# MCU.net
KiCad netlist of a schematic drawn in Altium Designer
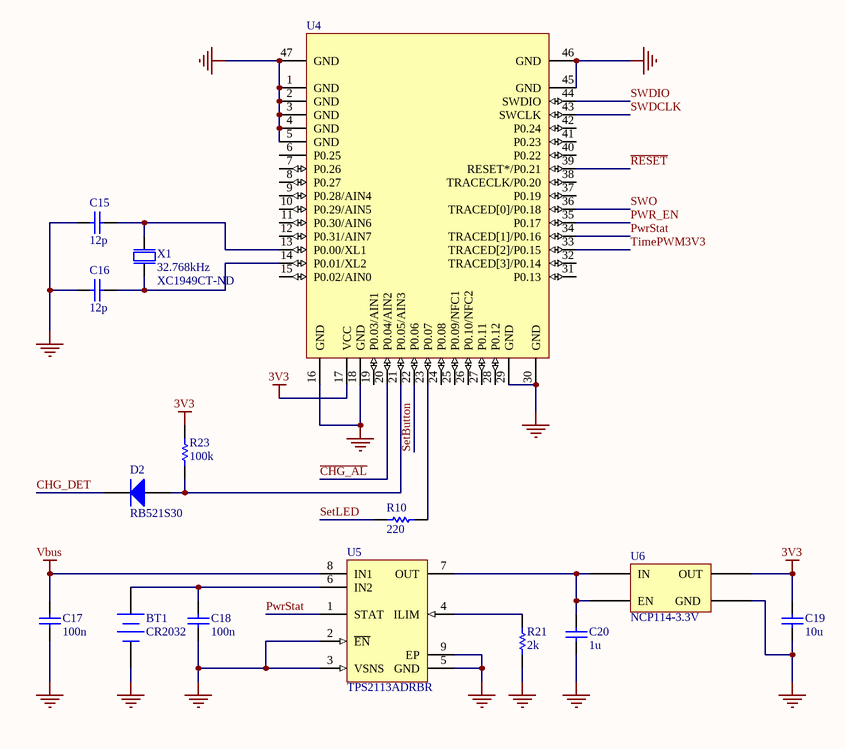
[diagram p0: MCU.SchDoc]

(export (version "E")
  (design (tool "Eeschema 10.0.6"))
  (components
    (comp (ref "BT1")
      (value "CR2032")
      (footprint "BK-912")
      (description "BATTERY RETAINER COIN 20MM SMD")
      (fields
        (field (name "MANUFACTURER") "Memory Protection Devices")
        (field (name "MANUFACTURER PART NUMBER") "BK-912-TR")
      )
      (libsource (lib "Connectors") (part "BK-912"))
    )
    (comp (ref "C15")
      (value "12p")
      (footprint "CAPC0402(1005)60_N")
      (description "CAP CER 12PF 50V C0G/NPO 0402")
      (fields
        (field (name "MANUFACTURER") "Yageo")
        (field (name "MANUFACTURER PART NUMBER") "CC0402FRNPO9BN120")
      )
      (libsource (lib "0402 Caps") (part "CC0402FRNPO9BN120"))
    )
    (comp (ref "C16")
      (value "12p")
      (footprint "CAPC0402(1005)60_N")
      (description "CAP CER 12PF 50V C0G/NPO 0402")
      (fields
        (field (name "MANUFACTURER") "Yageo")
        (field (name "MANUFACTURER PART NUMBER") "CC0402FRNPO9BN120")
      )
      (libsource (lib "0402 Caps") (part "CC0402FRNPO9BN120"))
    )
    (comp (ref "C17")
      (value "100n")
      (footprint "CAPC0402(1005)33_N")
      (description "CAP CER 0.1UF 25V X7R 0402")
      (fields
        (field (name "MANUFACTURER") "Yageo")
        (field (name "MANUFACTURER PART NUMBER") "CC0402KRX7R8BB104")
      )
      (libsource (lib "0402 Caps") (part "CC0402KRX7R8BB104"))
    )
    (comp (ref "C18")
      (value "100n")
      (footprint "CAPC0402(1005)33_N")
      (description "CAP CER 0.1UF 25V X7R 0402")
      (fields
        (field (name "MANUFACTURER") "Yageo")
        (field (name "MANUFACTURER PART NUMBER") "CC0402KRX7R8BB104")
      )
      (libsource (lib "0402 Caps") (part "CC0402KRX7R8BB104"))
    )
    (comp (ref "C19")
      (value "10u")
      (footprint "CAPC0603(1608)100_N")
      (description "Multilayer Ceramic Capacitors MLCC - SMD/SMT 0603 10uF 16volts X5R 10%")
      (fields
        (field (name "MANUFACTURER") "Murata")
        (field (name "MANUFACTURER PART NUMBER") "GRM188R61C106KAALD")
      )
      (libsource (lib "0603 Caps") (part "GRM188R61C106KAALD"))
    )
    (comp (ref "C20")
      (value "1u")
      (footprint "CAPC0603(1608)100_N")
      (description "CAP CER 1UF 16V X7R 0603")
      (fields
        (field (name "MANUFACTURER") "Samsung Electro-Mechanics")
        (field (name "MANUFACTURER PART NUMBER") "CL10B105MO8NNWC")
      )
      (libsource (lib "0603 Caps") (part "CL10B105MO8NNWC"))
    )
    (comp (ref "D2")
      (value "RB521S30")
      (footprint "SOD-523")
      (description "DIODE SCHOTTKY 30V 200MA SOD523F")
      (fields (field (name "MANUFACTURER") "ON Semiconductor / Fairchild"))
      (libsource (lib "Discretes") (part "RB521S30"))
    )
    (comp (ref "R10")
      (value "220")
      (footprint "RESC0402(1005)_N")
      (description "RES SMD 220 OHM 1% 1/16W 0402")
      (fields
        (field (name "MANUFACTURER") "Yageo")
        (field (name "MANUFACTURER PART NUMBER") "RC0402FR-07220RL")
      )
      (libsource (lib "0402 Resistors") (part "RC0402FR-07220RL"))
    )
    (comp (ref "R21")
      (value "2k")
      (footprint "RESC0402(1005)_N")
      (description "RES SMD 2K OHM 1% 1/16W 0402")
      (fields
        (field (name "MANUFACTURER") "Yageo")
        (field (name "MANUFACTURER PART NUMBER") "RC0402FR-072KL")
      )
      (libsource (lib "0402 Resistors") (part "RC0402FR-072KL"))
    )
    (comp (ref "R23")
      (value "100k")
      (footprint "RESC0402(1005)_N")
      (description "RES SMD 100K OHM 1% 1/16W 0402")
      (fields
        (field (name "MANUFACTURER") "Yageo")
        (field (name "MANUFACTURER PART NUMBER") "RC0402FR-07100KL")
      )
      (libsource (lib "0402 Resistors") (part "RC0402FR-07100KL"))
    )
    (comp (ref "U4")
      (value "BMD-300")
      (footprint "BMD-300")
      (description "Bluetooth 4.2 LE Module, nRF52832, 512kB Flash, 64kB RAM")
      (fields
        (field (name "PART NUMBER") "BMD-300-A")
        (field (name "MANUFACTURER") "Rigado")
        (field (name "ADDED BY") "Cam N")
      )
      (libsource (lib "BMD-300-Altium") (part "BMD-300-A"))
    )
    (comp (ref "U5")
      (value "TPS2113ADRBR")
      (footprint "VSON-8")
      (fields (field (name "MANUFACTURER") "Texas Instruments"))
      (libsource (lib "IC") (part "TPS2113ADRB"))
    )
    (comp (ref "U6")
      (value "NCP114-3.3V")
      (footprint "TSOP-5")
      (description "IC REG LINEAR 3.3V 300MA 5TSOP")
      (fields
        (field (name "MANUFACTURER") "ON Semiconductor")
        (field (name "MANUFACTURER PART NUMBER") "NCP114ASN330T1G")
      )
      (libsource (lib "IC") (part "NCP114ASN330T1G"))
    )
    (comp (ref "X1")
      (value "32.768kHz")
      (footprint "3215 XTAL")
      (description "CRYSTAL 32.7680KHZ 9PF SMD")
      (fields
        (field (name "SUPPLIER PART NUMBER 1") "XC1949CT-ND")
        (field (name "MANUFACTURER") "ECS International")
        (field (name "MANUFACTURER PART NUMBER") "ECS-.327-9-34B-C-TR")
      )
      (libsource (lib "Discretes") (part "ECS-.327-9-34B-C-TR"))
    )
  )
  (nets
    (net (code "1") (name "/CHG_DET") (class "Default")
      (node (ref "D2") (pin "1") (pinfunction "K_1") (pintype "passive"))
    )
    (net (code "2") (name "/PWR_EN") (class "Default")
      (node (ref "U4") (pin "35") (pinfunction "P0.17_35") (pintype "bidirectional"))
    )
    (net (code "3") (name "/PwrStat") (class "Default")
      (node (ref "U4") (pin "34") (pinfunction "TRACED[1]/P0.16_34") (pintype "bidirectional"))
      (node (ref "U5") (pin "1") (pinfunction "STAT_1") (pintype "tri_state"))
    )
    (net (code "4") (name "/SWDCLK") (class "Default")
      (node (ref "U4") (pin "43") (pinfunction "SWCLK_43") (pintype "bidirectional"))
    )
    (net (code "5") (name "/SWDIO") (class "Default")
      (node (ref "U4") (pin "44") (pinfunction "SWDIO_44") (pintype "bidirectional"))
    )
    (net (code "6") (name "/SWO") (class "Default")
      (node (ref "U4") (pin "36") (pinfunction "TRACED[0]/P0.18_36") (pintype "bidirectional"))
    )
    (net (code "7") (name "/SetButton") (class "Default")
      (node (ref "U4") (pin "22") (pinfunction "P0.06_22") (pintype "bidirectional"))
    )
    (net (code "8") (name "/SetLED") (class "Default")
      (node (ref "R10") (pin "1") (pinfunction "1_1") (pintype "passive"))
    )
    (net (code "9") (name "/TimePWM3V3") (class "Default")
      (node (ref "U4") (pin "33") (pinfunction "TRACED[2]/P0.15_33") (pintype "bidirectional"))
    )
    (net (code "10") (name "/~{CHG_AL}") (class "Default")
      (node (ref "U4") (pin "20") (pinfunction "P0.04/AIN2_20") (pintype "bidirectional"))
    )
    (net (code "11") (name "/~{RESET}") (class "Default")
      (node (ref "U4") (pin "39") (pinfunction "RESET*/P0.21_39") (pintype "bidirectional"))
    )
    (net (code "12") (name "3V3") (class "Default")
      (node (ref "C19") (pin "2") (pinfunction "2_2") (pintype "passive"))
      (node (ref "R23") (pin "2") (pinfunction "2_2") (pintype "passive"))
      (node (ref "U4") (pin "17") (pinfunction "VCC_17") (pintype "power_in"))
      (node (ref "U6") (pin "5") (pinfunction "OUT_5") (pintype "passive"))
    )
    (net (code "13") (name "GND") (class "Default")
      (node (ref "BT1") (pin "2") (pinfunction "-_2") (pintype "passive"))
      (node (ref "C15") (pin "1") (pinfunction "1_1") (pintype "passive"))
      (node (ref "C16") (pin "1") (pinfunction "1_1") (pintype "passive"))
      (node (ref "C17") (pin "1") (pinfunction "1_1") (pintype "passive"))
      (node (ref "C18") (pin "1") (pinfunction "1_1") (pintype "passive"))
      (node (ref "C19") (pin "1") (pinfunction "1_1") (pintype "passive"))
      (node (ref "C20") (pin "1") (pinfunction "1_1") (pintype "passive"))
      (node (ref "R21") (pin "1") (pinfunction "1_1") (pintype "passive"))
      (node (ref "U4") (pin "1") (pinfunction "GND_1") (pintype "power_in"))
      (node (ref "U4") (pin "16") (pinfunction "GND_16") (pintype "power_in"))
      (node (ref "U4") (pin "18") (pinfunction "GND_18") (pintype "power_in"))
      (node (ref "U4") (pin "2") (pinfunction "GND_2") (pintype "power_in"))
      (node (ref "U4") (pin "29") (pinfunction "GND_29") (pintype "power_in"))
      (node (ref "U4") (pin "3") (pinfunction "GND_3") (pintype "power_in"))
      (node (ref "U4") (pin "30") (pinfunction "GND_30") (pintype "power_in"))
      (node (ref "U4") (pin "4") (pinfunction "GND_4") (pintype "power_in"))
      (node (ref "U4") (pin "45") (pinfunction "GND_45") (pintype "power_in"))
      (node (ref "U4") (pin "46") (pinfunction "GND_46") (pintype "power_in"))
      (node (ref "U4") (pin "47") (pinfunction "GND_47") (pintype "power_in"))
      (node (ref "U4") (pin "5") (pinfunction "GND_5") (pintype "power_in"))
      (node (ref "U5") (pin "2") (pinfunction "~{EN}_2") (pintype "input"))
      (node (ref "U5") (pin "3") (pinfunction "VSNS_3") (pintype "input"))
      (node (ref "U5") (pin "5") (pinfunction "GND_5") (pintype "power_in"))
      (node (ref "U5") (pin "9") (pinfunction "EP_9") (pintype "power_in"))
      (node (ref "U6") (pin "2") (pinfunction "GND_2") (pintype "passive"))
    )
    (net (code "14") (name "Net-(BT1-+)") (class "Default")
      (node (ref "BT1") (pin "1") (pinfunction "+_1") (pintype "passive"))
      (node (ref "C18") (pin "2") (pinfunction "2_2") (pintype "passive"))
      (node (ref "U5") (pin "6") (pinfunction "IN2_6") (pintype "power_in"))
    )
    (net (code "15") (name "Net-(D2-A)") (class "Default")
      (node (ref "D2") (pin "2") (pinfunction "A_2") (pintype "passive"))
      (node (ref "R23") (pin "1") (pinfunction "1_1") (pintype "passive"))
      (node (ref "U4") (pin "21") (pinfunction "P0.05/AIN3_21") (pintype "bidirectional"))
    )
    (net (code "16") (name "Net-(U4-P0.00{slash}XL1)") (class "Default")
      (node (ref "C15") (pin "2") (pinfunction "2_2") (pintype "passive"))
      (node (ref "U4") (pin "13") (pinfunction "P0.00/XL1_13") (pintype "bidirectional"))
      (node (ref "X1") (pin "2") (pinfunction "2_2") (pintype "passive"))
    )
    (net (code "17") (name "Net-(U4-P0.01{slash}XL2)") (class "Default")
      (node (ref "C16") (pin "2") (pinfunction "2_2") (pintype "passive"))
      (node (ref "U4") (pin "14") (pinfunction "P0.01/XL2_14") (pintype "bidirectional"))
      (node (ref "X1") (pin "1") (pinfunction "1_1") (pintype "passive"))
    )
    (net (code "18") (name "Net-(U4-P0.07)") (class "Default")
      (node (ref "R10") (pin "2") (pinfunction "2_2") (pintype "passive"))
      (node (ref "U4") (pin "23") (pinfunction "P0.07_23") (pintype "bidirectional"))
    )
    (net (code "19") (name "Net-(U5-ILIM)") (class "Default")
      (node (ref "R21") (pin "2") (pinfunction "2_2") (pintype "passive"))
      (node (ref "U5") (pin "4") (pinfunction "ILIM_4") (pintype "input"))
    )
    (net (code "20") (name "Net-(U5-OUT)") (class "Default")
      (node (ref "C20") (pin "2") (pinfunction "2_2") (pintype "passive"))
      (node (ref "U5") (pin "7") (pinfunction "OUT_7") (pintype "power_in"))
      (node (ref "U6") (pin "1") (pinfunction "IN_1") (pintype "passive"))
      (node (ref "U6") (pin "3") (pinfunction "EN_3") (pintype "passive"))
    )
    (net (code "21") (name "Vbus") (class "Default")
      (node (ref "C17") (pin "2") (pinfunction "2_2") (pintype "passive"))
      (node (ref "U5") (pin "8") (pinfunction "IN1_8") (pintype "power_in"))
    )
    (net (code "22") (name "unconnected-(U4-P0.02{slash}AIN0-Pad15)") (class "Default")
      (node (ref "U4") (pin "15") (pinfunction "P0.02/AIN0_15") (pintype "bidirectional"))
    )
    (net (code "23") (name "unconnected-(U4-P0.03{slash}AIN1-Pad19)") (class "Default")
      (node (ref "U4") (pin "19") (pinfunction "P0.03/AIN1_19") (pintype "bidirectional"))
    )
    (net (code "24") (name "unconnected-(U4-P0.08-Pad24)") (class "Default")
      (node (ref "U4") (pin "24") (pinfunction "P0.08_24") (pintype "bidirectional"))
    )
    (net (code "25") (name "unconnected-(U4-P0.09{slash}NFC1-Pad25)") (class "Default")
      (node (ref "U4") (pin "25") (pinfunction "P0.09/NFC1_25") (pintype "bidirectional"))
    )
    (net (code "26") (name "unconnected-(U4-P0.10{slash}NFC2-Pad26)") (class "Default")
      (node (ref "U4") (pin "26") (pinfunction "P0.10/NFC2_26") (pintype "bidirectional"))
    )
    (net (code "27") (name "unconnected-(U4-P0.11-Pad27)") (class "Default")
      (node (ref "U4") (pin "27") (pinfunction "P0.11_27") (pintype "bidirectional"))
    )
    (net (code "28") (name "unconnected-(U4-P0.12-Pad28)") (class "Default")
      (node (ref "U4") (pin "28") (pinfunction "P0.12_28") (pintype "bidirectional"))
    )
    (net (code "29") (name "unconnected-(U4-P0.13-Pad31)") (class "Default")
      (node (ref "U4") (pin "31") (pinfunction "P0.13_31") (pintype "bidirectional"))
    )
    (net (code "30") (name "unconnected-(U4-P0.19-Pad37)") (class "Default")
      (node (ref "U4") (pin "37") (pinfunction "P0.19_37") (pintype "bidirectional"))
    )
    (net (code "31") (name "unconnected-(U4-P0.22-Pad40)") (class "Default")
      (node (ref "U4") (pin "40") (pinfunction "P0.22_40") (pintype "bidirectional"))
    )
    (net (code "32") (name "unconnected-(U4-P0.23-Pad41)") (class "Default")
      (node (ref "U4") (pin "41") (pinfunction "P0.23_41") (pintype "bidirectional"))
    )
    (net (code "33") (name "unconnected-(U4-P0.24-Pad42)") (class "Default")
      (node (ref "U4") (pin "42") (pinfunction "P0.24_42") (pintype "bidirectional"))
    )
    (net (code "34") (name "unconnected-(U4-P0.25-Pad6)") (class "Default")
      (node (ref "U4") (pin "6") (pinfunction "P0.25_6") (pintype "power_in"))
    )
    (net (code "35") (name "unconnected-(U4-P0.26-Pad7)") (class "Default")
      (node (ref "U4") (pin "7") (pinfunction "P0.26_7") (pintype "bidirectional"))
    )
    (net (code "36") (name "unconnected-(U4-P0.27-Pad8)") (class "Default")
      (node (ref "U4") (pin "8") (pinfunction "P0.27_8") (pintype "bidirectional"))
    )
    (net (code "37") (name "unconnected-(U4-P0.28{slash}AIN4-Pad9)") (class "Default")
      (node (ref "U4") (pin "9") (pinfunction "P0.28/AIN4_9") (pintype "bidirectional"))
    )
    (net (code "38") (name "unconnected-(U4-P0.29{slash}AIN5-Pad10)") (class "Default")
      (node (ref "U4") (pin "10") (pinfunction "P0.29/AIN5_10") (pintype "bidirectional"))
    )
    (net (code "39") (name "unconnected-(U4-P0.30{slash}AIN6-Pad11)") (class "Default")
      (node (ref "U4") (pin "11") (pinfunction "P0.30/AIN6_11") (pintype "bidirectional"))
    )
    (net (code "40") (name "unconnected-(U4-P0.31{slash}AIN7-Pad12)") (class "Default")
      (node (ref "U4") (pin "12") (pinfunction "P0.31/AIN7_12") (pintype "bidirectional"))
    )
    (net (code "41") (name "unconnected-(U4-TRACECLK{slash}P0.20-Pad38)") (class "Default")
      (node (ref "U4") (pin "38") (pinfunction "TRACECLK/P0.20_38") (pintype "bidirectional"))
    )
    (net (code "42") (name "unconnected-(U4-TRACED[3]{slash}P0.14-Pad32)") (class "Default")
      (node (ref "U4") (pin "32") (pinfunction "TRACED[3]/P0.14_32") (pintype "bidirectional"))
    )
  )
)
